# coil_driver.net
KiCad netlist of a schematic drawn in Altium Designer
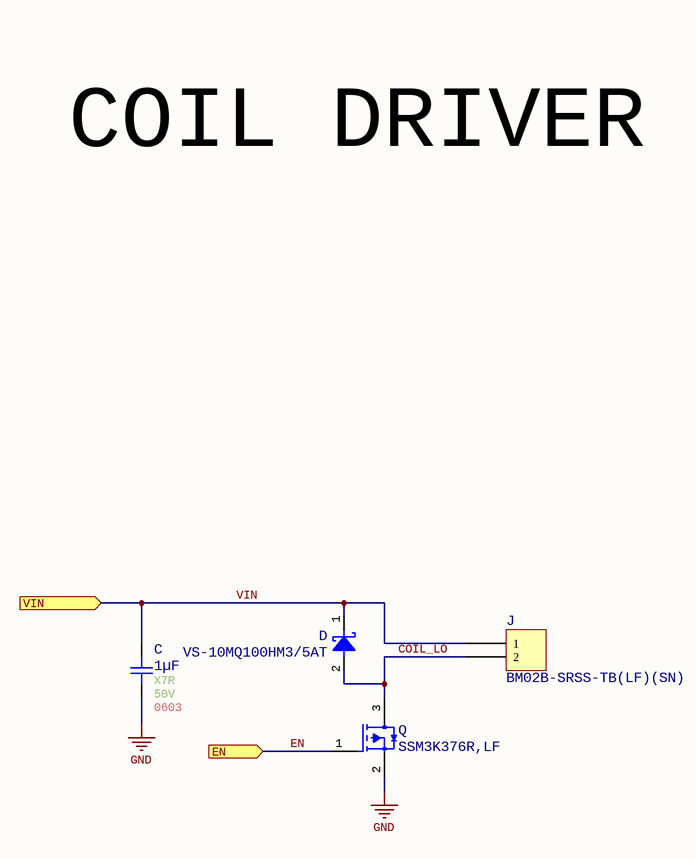
[diagram p0: coil_driver.SchDoc]

(export (version "E")
  (design (tool "Eeschema 10.0.6"))
  (components
    (comp (ref "C")
      (value "1µF")
      (footprint "Generic 0603 Capacitor")
      (description "Automotive Grade, Mlcc, 0603, X7R, 5")
      (fields
        (field (name "TEMPERATURE COEFFICIENT") "X7R")
        (field (name "VOLTAGE RATING") "50V")
        (field (name "CASE/PACKAGE") "0603")
        (field (name "TOLERANCE") "10%")
        (field (name "Comment") "CGA3E3X7R1H105K080AB")
      )
      (libsource (lib "Raise Robotics") (part "Unpolarized Capacitor"))
    )
    (comp (ref "D")
      (value "VS-10MQ100HM3/5AT")
      (footprint "FP-95400-MFG")
      (description "Rectifier Diode, Schottky, 1 Phase, 1 Element, 1.5A, 100V V(RRM), Silicon, DO-214AC")
      (libsource (lib "Raise Robotics") (part "Generic 2 pin Diode"))
    )
    (comp (ref "J")
      (value "BM02B-SRSS-TB(LF)(SN)")
      (footprint "JST BM02B-SRSS-TB")
      (description "CONN HEADER SMD 2POS 1MM")
      (fields (field (name "MANUFACTURER") "JST Sales America Inc."))
      (libsource (lib "Celestial Altium Library - altium_library") (part "2 Pin"))
    )
    (comp (ref "Q")
      (value "SSM3K376R,LF")
      (footprint "SSM3K376R,LF")
      (description "Transistor MOSFET N-CH 30V 4A 3-Pin SOT-23F Emboss T/R")
      (libsource (lib "Raise Robotics") (part "SSM3K376R,LF"))
    )
  )
  (nets
    (net (code "1") (name "/COIL_LO") (class "Default")
      (node (ref "D") (pin "2") (pinfunction "A_2") (pintype "passive"))
      (node (ref "J") (pin "2") (pinfunction "2_2") (pintype "passive"))
      (node (ref "Q") (pin "3") (pinfunction "D_3") (pintype "passive"))
    )
    (net (code "2") (name "/EN") (class "Default")
      (node (ref "Q") (pin "1") (pinfunction "G_1") (pintype "passive"))
    )
    (net (code "3") (name "/VIN") (class "Default")
      (node (ref "C") (pin "2") (pinfunction "2_2") (pintype "passive"))
      (node (ref "D") (pin "1") (pinfunction "C_1") (pintype "passive"))
      (node (ref "J") (pin "1") (pinfunction "1_1") (pintype "passive"))
    )
    (net (code "4") (name "GND") (class "Default")
      (node (ref "C") (pin "1") (pinfunction "1_1") (pintype "passive"))
      (node (ref "Q") (pin "2") (pinfunction "S_2") (pintype "passive"))
    )
  )
)
